# Circuit.net
KiCad netlist of a schematic drawn in Altium Designer
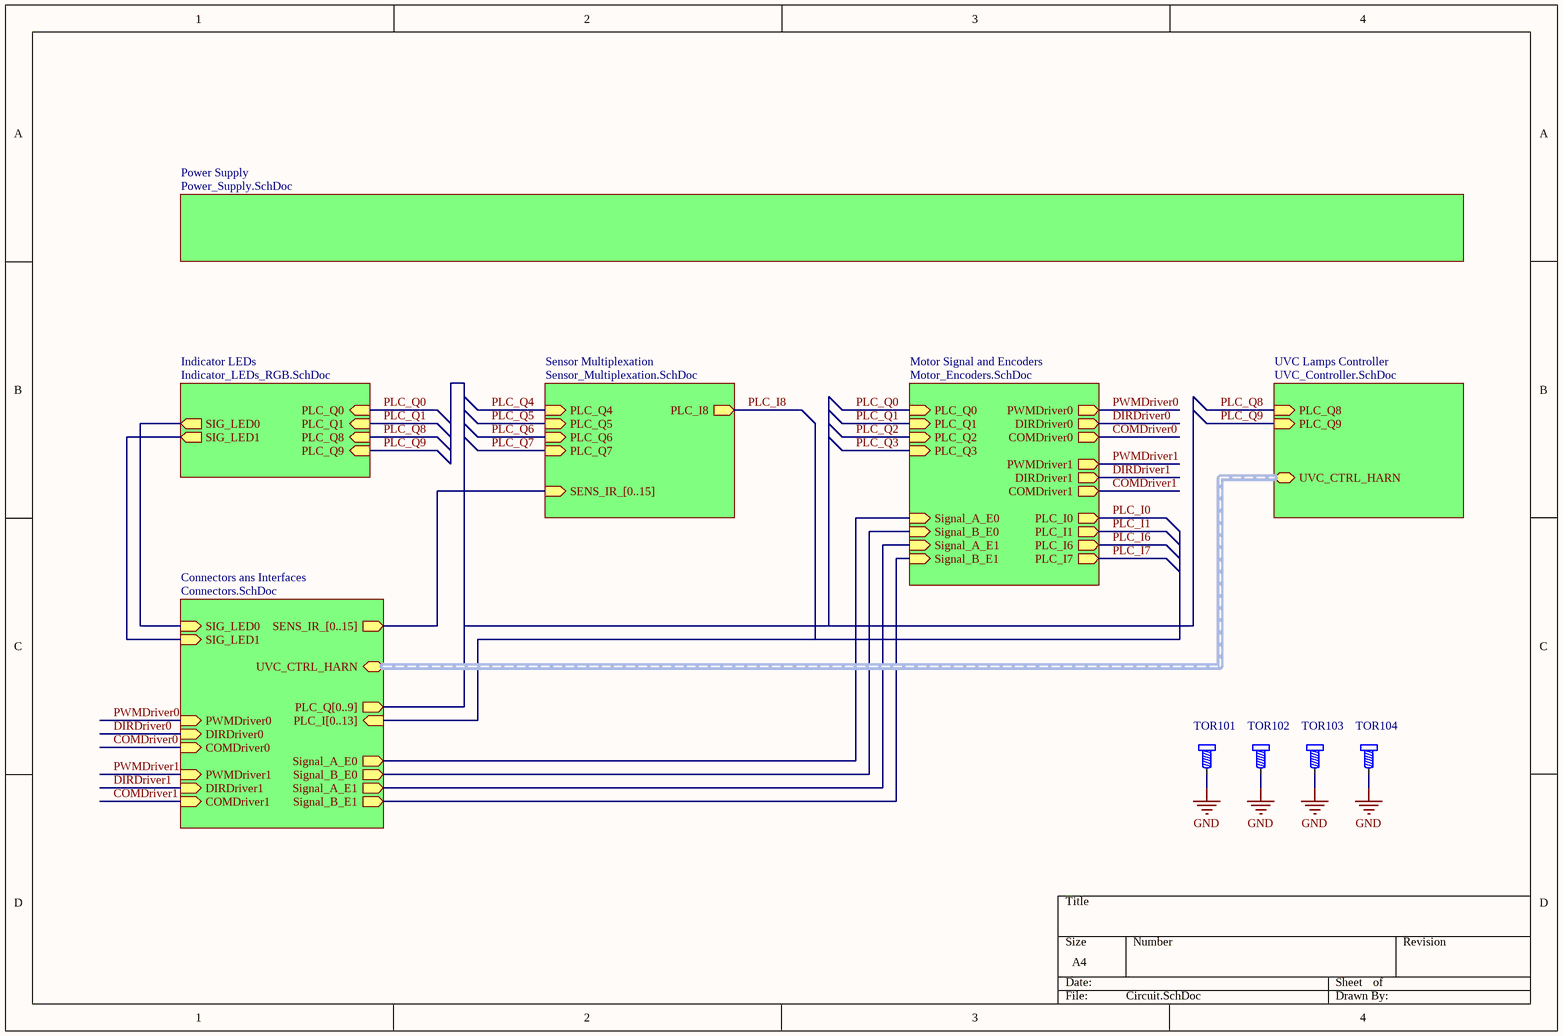
[diagram p0: Circuit.SchDoc]

(export (version "E")
  (design (tool "Eeschema 10.0.6"))
  (components
    (comp (ref "TOR101")
      (value "SUJETADOR")
      (footprint "TOR_ALEM_M3")
      (description "Agujero para tornillo ed sujecion ed placa")
      (libsource (lib "RUF-Dispositivos-Grales") (part "Tornillos Sujecion"))
    )
    (comp (ref "TOR102")
      (value "SUJETADOR")
      (footprint "TOR_ALEM_M3")
      (description "Agujero para tornillo ed sujecion ed placa")
      (libsource (lib "RUF-Dispositivos-Grales") (part "Tornillos Sujecion"))
    )
    (comp (ref "TOR103")
      (value "SUJETADOR")
      (footprint "TOR_ALEM_M3")
      (description "Agujero para tornillo ed sujecion ed placa")
      (libsource (lib "RUF-Dispositivos-Grales") (part "Tornillos Sujecion"))
    )
    (comp (ref "TOR104")
      (value "SUJETADOR")
      (footprint "TOR_ALEM_M3")
      (description "Agujero para tornillo ed sujecion ed placa")
      (libsource (lib "RUF-Dispositivos-Grales") (part "Tornillos Sujecion"))
    )
  )
  (nets
    (net (code "32") (name "GND") (class "Default")
      (node (ref "TOR101") (pin "1") (pinfunction "1_1") (pintype "passive"))
      (node (ref "TOR102") (pin "1") (pinfunction "1_1") (pintype "passive"))
      (node (ref "TOR103") (pin "1") (pinfunction "1_1") (pintype "passive"))
      (node (ref "TOR104") (pin "1") (pinfunction "1_1") (pintype "passive"))
    )
  )
)
